# AudioADCA.net
KiCad netlist of a schematic drawn in Altium Designer
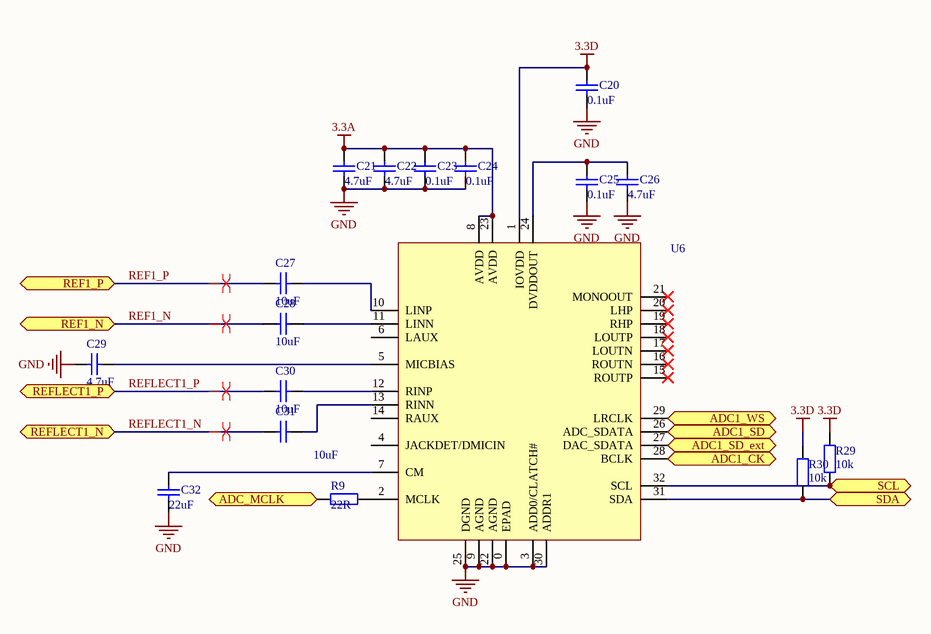
[diagram p0: AudioADCA.SchDoc]

(export (version "E")
  (design (tool "Eeschema 10.0.6"))
  (components
    (comp (ref "C20")
      (value "0.1uF")
      (footprint "0402")
      (description "Capacitor")
      (fields (field (name "PUBLISHER") "Altium Limited"))
      (libsource (lib "RTC6705") (part "Cap"))
    )
    (comp (ref "C21")
      (value "4.7uF")
      (footprint "0805")
      (description "Capacitor")
      (fields (field (name "PUBLISHER") "Altium Limited"))
      (libsource (lib "RTC6705") (part "Cap"))
    )
    (comp (ref "C22")
      (value "4.7uF")
      (footprint "0805")
      (description "Capacitor")
      (fields (field (name "PUBLISHER") "Altium Limited"))
      (libsource (lib "RTC6705") (part "Cap"))
    )
    (comp (ref "C23")
      (value "0.1uF")
      (footprint "0402")
      (description "Capacitor")
      (fields (field (name "PUBLISHER") "Altium Limited"))
      (libsource (lib "RTC6705") (part "Cap"))
    )
    (comp (ref "C24")
      (value "0.1uF")
      (footprint "0402")
      (description "Capacitor")
      (fields (field (name "PUBLISHER") "Altium Limited"))
      (libsource (lib "RTC6705") (part "Cap"))
    )
    (comp (ref "C25")
      (value "0.1uF")
      (footprint "0402")
      (description "Capacitor")
      (fields (field (name "PUBLISHER") "Altium Limited"))
      (libsource (lib "RTC6705") (part "Cap"))
    )
    (comp (ref "C26")
      (value "4.7uF")
      (footprint "0805")
      (description "Capacitor")
      (fields (field (name "PUBLISHER") "Altium Limited"))
      (libsource (lib "RTC6705") (part "Cap"))
    )
    (comp (ref "C27")
      (value "10uF")
      (footprint "0402")
      (description "Capacitor")
      (fields (field (name "PUBLISHER") "Altium Limited"))
      (libsource (lib "RTC6705") (part "Cap"))
    )
    (comp (ref "C28")
      (value "10uF")
      (footprint "0402")
      (description "Capacitor")
      (fields (field (name "PUBLISHER") "Altium Limited"))
      (libsource (lib "RTC6705") (part "Cap"))
    )
    (comp (ref "C29")
      (value "4.7uF")
      (footprint "0402")
      (description "Capacitor")
      (fields (field (name "PUBLISHER") "Altium Limited"))
      (libsource (lib "RTC6705") (part "Cap"))
    )
    (comp (ref "C30")
      (value "10uF")
      (footprint "0402")
      (description "Capacitor")
      (fields (field (name "PUBLISHER") "Altium Limited"))
      (libsource (lib "RTC6705") (part "Cap"))
    )
    (comp (ref "C31")
      (value "10uF")
      (footprint "0402")
      (description "Capacitor")
      (fields (field (name "PUBLISHER") "Altium Limited"))
      (libsource (lib "RTC6705") (part "Cap"))
    )
    (comp (ref "C32")
      (value "22uF")
      (footprint "0805")
      (description "Capacitor")
      (fields (field (name "PUBLISHER") "Altium Limited"))
      (libsource (lib "RTC6705") (part "Cap"))
    )
    (comp (ref "R9")
      (value "22R")
      (footprint "0402")
      (description "Resistor")
      (fields (field (name "PUBLISHER") "Altium Limited"))
      (libsource (lib "") (part "Res2_1"))
    )
    (comp (ref "R29")
      (value "10k")
      (footprint "0402")
      (description "Resistor")
      (fields (field (name "Comment") "Res2") (field (name "PUBLISHER") "Altium Limited"))
      (libsource (lib "RTC6705") (part "Res2"))
    )
    (comp (ref "R30")
      (value "10k")
      (footprint "0402")
      (description "Resistor")
      (fields (field (name "Comment") "Res2") (field (name "PUBLISHER") "Altium Limited"))
      (libsource (lib "RTC6705") (part "Res2"))
    )
    (comp (ref "U6") (value "ADAU1761") (footprint "ADAU1761") (libsource (lib "ADAU1761") (part "ADAU1761")))
  )
  (nets
    (net (code "1") (name "/ADC1_CK") (class "Default")
      (node (ref "U6") (pin "28") (pinfunction "BCLK_28") (pintype "passive"))
    )
    (net (code "2") (name "/ADC1_SD") (class "Default")
      (node (ref "U6") (pin "26") (pinfunction "ADC_SDATA_26") (pintype "passive"))
    )
    (net (code "3") (name "/ADC1_SD_ext") (class "Default")
      (node (ref "U6") (pin "27") (pinfunction "DAC_SDATA_27") (pintype "passive"))
    )
    (net (code "4") (name "/ADC1_WS") (class "Default")
      (node (ref "U6") (pin "29") (pinfunction "LRCLK_29") (pintype "passive"))
    )
    (net (code "5") (name "/ADC_MCLK") (class "Default")
      (node (ref "R9") (pin "2") (pinfunction "2_2") (pintype "passive"))
    )
    (net (code "6") (name "/REF1_N") (class "Default")
      (node (ref "C28") (pin "2") (pinfunction "2_2") (pintype "passive"))
    )
    (net (code "7") (name "/REF1_P") (class "Default")
      (node (ref "C27") (pin "2") (pinfunction "2_2") (pintype "passive"))
    )
    (net (code "8") (name "/REFLECT1_N") (class "Default")
      (node (ref "C31") (pin "1") (pinfunction "1_1") (pintype "passive"))
    )
    (net (code "9") (name "/REFLECT1_P") (class "Default")
      (node (ref "C30") (pin "1") (pinfunction "1_1") (pintype "passive"))
    )
    (net (code "10") (name "/SCL") (class "Default")
      (node (ref "R29") (pin "1") (pinfunction "1_1") (pintype "passive"))
      (node (ref "U6") (pin "32") (pinfunction "SCL_32") (pintype "passive"))
    )
    (net (code "11") (name "/SDA") (class "Default")
      (node (ref "R30") (pin "1") (pinfunction "1_1") (pintype "passive"))
      (node (ref "U6") (pin "31") (pinfunction "SDA_31") (pintype "passive"))
    )
    (net (code "12") (name "3.3A") (class "Default")
      (node (ref "C21") (pin "2") (pinfunction "2_2") (pintype "passive"))
      (node (ref "C22") (pin "2") (pinfunction "2_2") (pintype "passive"))
      (node (ref "C23") (pin "2") (pinfunction "2_2") (pintype "passive"))
      (node (ref "C24") (pin "2") (pinfunction "2_2") (pintype "passive"))
      (node (ref "U6") (pin "23") (pinfunction "AVDD_23") (pintype "passive"))
      (node (ref "U6") (pin "8") (pinfunction "AVDD_8") (pintype "passive"))
    )
    (net (code "13") (name "3.3D") (class "Default")
      (node (ref "C20") (pin "2") (pinfunction "2_2") (pintype "passive"))
      (node (ref "R29") (pin "2") (pinfunction "2_2") (pintype "passive"))
      (node (ref "R30") (pin "2") (pinfunction "2_2") (pintype "passive"))
      (node (ref "U6") (pin "1") (pinfunction "IOVDD_1") (pintype "passive"))
    )
    (net (code "14") (name "GND") (class "Default")
      (node (ref "C20") (pin "1") (pinfunction "1_1") (pintype "passive"))
      (node (ref "C21") (pin "1") (pinfunction "1_1") (pintype "passive"))
      (node (ref "C22") (pin "1") (pinfunction "1_1") (pintype "passive"))
      (node (ref "C23") (pin "1") (pinfunction "1_1") (pintype "passive"))
      (node (ref "C24") (pin "1") (pinfunction "1_1") (pintype "passive"))
      (node (ref "C25") (pin "1") (pinfunction "1_1") (pintype "passive"))
      (node (ref "C26") (pin "1") (pinfunction "1_1") (pintype "passive"))
      (node (ref "C29") (pin "1") (pinfunction "1_1") (pintype "passive"))
      (node (ref "C32") (pin "1") (pinfunction "1_1") (pintype "passive"))
      (node (ref "U6") (pin "0") (pinfunction "EPAD_0") (pintype "passive"))
      (node (ref "U6") (pin "22") (pinfunction "AGND_22") (pintype "passive"))
      (node (ref "U6") (pin "25") (pinfunction "DGND_25") (pintype "passive"))
      (node (ref "U6") (pin "3") (pinfunction "ADD0/CLATCH#_3") (pintype "passive"))
      (node (ref "U6") (pin "30") (pinfunction "ADDR1_30") (pintype "passive"))
      (node (ref "U6") (pin "9") (pinfunction "AGND_9") (pintype "passive"))
    )
    (net (code "15") (name "Net-(U6-CM)") (class "Default")
      (node (ref "C32") (pin "2") (pinfunction "2_2") (pintype "passive"))
      (node (ref "U6") (pin "7") (pinfunction "CM_7") (pintype "passive"))
    )
    (net (code "16") (name "Net-(U6-DVDDOUT)") (class "Default")
      (node (ref "C25") (pin "2") (pinfunction "2_2") (pintype "passive"))
      (node (ref "C26") (pin "2") (pinfunction "2_2") (pintype "passive"))
      (node (ref "U6") (pin "24") (pinfunction "DVDDOUT_24") (pintype "passive"))
    )
    (net (code "17") (name "Net-(U6-LINN)") (class "Default")
      (node (ref "C28") (pin "1") (pinfunction "1_1") (pintype "passive"))
      (node (ref "U6") (pin "11") (pinfunction "LINN_11") (pintype "passive"))
    )
    (net (code "18") (name "Net-(U6-LINP)") (class "Default")
      (node (ref "C27") (pin "1") (pinfunction "1_1") (pintype "passive"))
      (node (ref "U6") (pin "10") (pinfunction "LINP_10") (pintype "passive"))
    )
    (net (code "19") (name "Net-(U6-MCLK)") (class "Default")
      (node (ref "R9") (pin "1") (pinfunction "1_1") (pintype "passive"))
      (node (ref "U6") (pin "2") (pinfunction "MCLK_2") (pintype "passive"))
    )
    (net (code "20") (name "Net-(U6-MICBIAS)") (class "Default")
      (node (ref "C29") (pin "2") (pinfunction "2_2") (pintype "passive"))
      (node (ref "U6") (pin "5") (pinfunction "MICBIAS_5") (pintype "passive"))
    )
    (net (code "21") (name "Net-(U6-RINN)") (class "Default")
      (node (ref "C31") (pin "2") (pinfunction "2_2") (pintype "passive"))
      (node (ref "U6") (pin "13") (pinfunction "RINN_13") (pintype "passive"))
    )
    (net (code "22") (name "Net-(U6-RINP)") (class "Default")
      (node (ref "C30") (pin "2") (pinfunction "2_2") (pintype "passive"))
      (node (ref "U6") (pin "12") (pinfunction "RINP_12") (pintype "passive"))
    )
    (net (code "23") (name "unconnected-(U6-JACKDET{slash}DMICIN-Pad4)") (class "Default")
      (node (ref "U6") (pin "4") (pinfunction "JACKDET/DMICIN_4") (pintype "passive"))
    )
    (net (code "24") (name "unconnected-(U6-LAUX-Pad6)") (class "Default")
      (node (ref "U6") (pin "6") (pinfunction "LAUX_6") (pintype "passive"))
    )
    (net (code "25") (name "unconnected-(U6-LHP-Pad20)") (class "Default")
      (node (ref "U6") (pin "20") (pinfunction "LHP_20") (pintype "passive+no_connect"))
    )
    (net (code "26") (name "unconnected-(U6-LOUTN-Pad17)") (class "Default")
      (node (ref "U6") (pin "17") (pinfunction "LOUTN_17") (pintype "passive+no_connect"))
    )
    (net (code "27") (name "unconnected-(U6-LOUTP-Pad18)") (class "Default")
      (node (ref "U6") (pin "18") (pinfunction "LOUTP_18") (pintype "passive+no_connect"))
    )
    (net (code "28") (name "unconnected-(U6-MONOOUT-Pad21)") (class "Default")
      (node (ref "U6") (pin "21") (pinfunction "MONOOUT_21") (pintype "passive+no_connect"))
    )
    (net (code "29") (name "unconnected-(U6-RAUX-Pad14)") (class "Default")
      (node (ref "U6") (pin "14") (pinfunction "RAUX_14") (pintype "passive"))
    )
    (net (code "30") (name "unconnected-(U6-RHP-Pad19)") (class "Default")
      (node (ref "U6") (pin "19") (pinfunction "RHP_19") (pintype "passive+no_connect"))
    )
    (net (code "31") (name "unconnected-(U6-ROUTN-Pad16)") (class "Default")
      (node (ref "U6") (pin "16") (pinfunction "ROUTN_16") (pintype "passive+no_connect"))
    )
    (net (code "32") (name "unconnected-(U6-ROUTP-Pad15)") (class "Default")
      (node (ref "U6") (pin "15") (pinfunction "ROUTP_15") (pintype "passive+no_connect"))
    )
  )
)
